# UBL_Distribution_V1p0.net
KiCad netlist of a schematic drawn in EAGLE
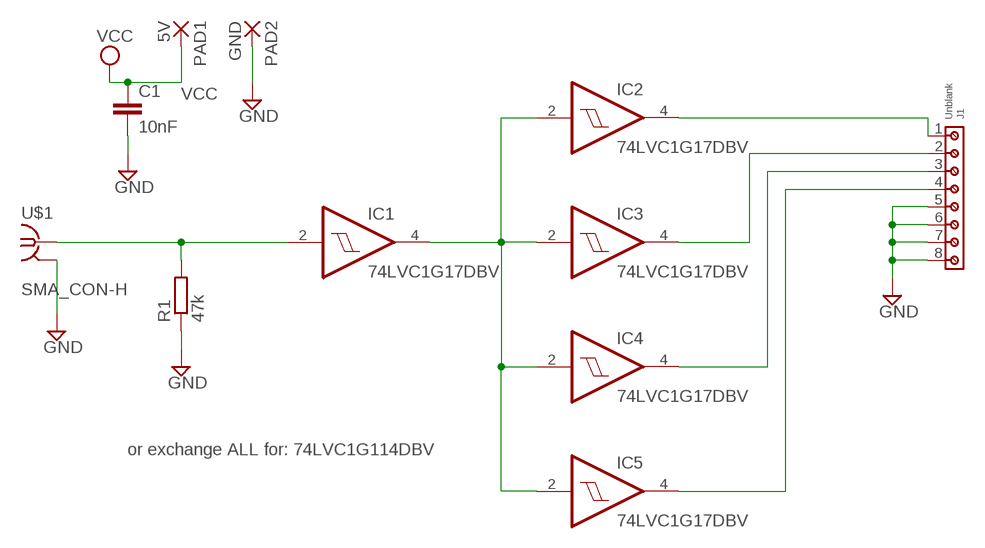
[diagram p0: schematic, sheet 1]

(export (version "E")
  (design (tool "Eeschema 10.0.6"))
  (components
    (comp (ref "C1")
      (value "10nF")
      (footprint "eagle-import:C0805")
      (libsource (lib "eagle-import") (part "C-EUC0805"))
    )
    (comp (ref "IC1")
      (value "74LVC1G17DBV")
      (footprint "eagle-import:SOT23-5")
      (libsource (lib "eagle-import") (part "741G17DBVLVC"))
    )
    (comp (ref "IC2")
      (value "74LVC1G17DBV")
      (footprint "eagle-import:SOT23-5")
      (libsource (lib "eagle-import") (part "741G17DBVLVC"))
    )
    (comp (ref "IC3")
      (value "74LVC1G17DBV")
      (footprint "eagle-import:SOT23-5")
      (libsource (lib "eagle-import") (part "741G17DBVLVC"))
    )
    (comp (ref "IC4")
      (value "74LVC1G17DBV")
      (footprint "eagle-import:SOT23-5")
      (libsource (lib "eagle-import") (part "741G17DBVLVC"))
    )
    (comp (ref "IC5")
      (value "74LVC1G17DBV")
      (footprint "eagle-import:SOT23-5")
      (libsource (lib "eagle-import") (part "741G17DBVLVC"))
    )
    (comp (ref "J1")
      (value "Unblank")
      (footprint "eagle-import:691210910008")
      (libsource (lib "eagle-import") (part "691210910008"))
    )
    (comp (ref "PAD1")
      (value "5V")
      (footprint "eagle-import:SMD2,54-5,08")
      (libsource (lib "eagle-import") (part "SMD5"))
    )
    (comp (ref "PAD2")
      (value "GND")
      (footprint "eagle-import:SMD2,54-5,08")
      (libsource (lib "eagle-import") (part "SMD5"))
    )
    (comp (ref "R1")
      (value "47k")
      (footprint "eagle-import:R0805")
      (libsource (lib "eagle-import") (part "R-EU_R0805"))
    )
    (comp (ref "U$1")
      (value "SMA_CON-H")
      (footprint "eagle-import:BU-SMA-H")
      (libsource (lib "eagle-import") (part "SMA_CON-H"))
    )
  )
  (nets
    (net (code "1") (name "GND") (class "Default")
      (node (ref "C1") (pin "2") (pinfunction "2_2") (pintype "passive"))
      (node (ref "J1") (pin "5") (pinfunction "5_5") (pintype "passive"))
      (node (ref "J1") (pin "6") (pinfunction "6_6") (pintype "passive"))
      (node (ref "J1") (pin "7") (pinfunction "7_7") (pintype "passive"))
      (node (ref "J1") (pin "8") (pinfunction "8_8") (pintype "passive"))
      (node (ref "PAD2") (pin "1") (pinfunction "P_1") (pintype "passive"))
      (node (ref "R1") (pin "1") (pinfunction "1_1") (pintype "passive"))
      (node (ref "U$1") (pin "2") (pinfunction "GND_2") (pintype "passive"))
      (node (ref "U$1") (pin "3") (pinfunction "GND_3") (pintype "passive"))
      (node (ref "U$1") (pin "4") (pinfunction "GND_4") (pintype "passive"))
      (node (ref "U$1") (pin "5") (pinfunction "GND_5") (pintype "passive"))
    )
    (net (code "2") (name "Net-(IC1A-I)") (class "Default")
      (node (ref "IC1") (pin "2") (pinfunction "I_2") (pintype "input"))
      (node (ref "R1") (pin "2") (pinfunction "2_2") (pintype "passive"))
      (node (ref "U$1") (pin "1") (pinfunction "1_1") (pintype "passive"))
    )
    (net (code "3") (name "Net-(IC1A-O)") (class "Default")
      (node (ref "IC1") (pin "4") (pinfunction "O_4") (pintype "output"))
      (node (ref "IC2") (pin "2") (pinfunction "I_2") (pintype "input"))
      (node (ref "IC3") (pin "2") (pinfunction "I_2") (pintype "input"))
      (node (ref "IC4") (pin "2") (pinfunction "I_2") (pintype "input"))
      (node (ref "IC5") (pin "2") (pinfunction "I_2") (pintype "input"))
    )
    (net (code "4") (name "Net-(IC2A-O)") (class "Default")
      (node (ref "IC2") (pin "4") (pinfunction "O_4") (pintype "output"))
      (node (ref "J1") (pin "1") (pinfunction "1_1") (pintype "passive"))
    )
    (net (code "5") (name "Net-(IC3A-O)") (class "Default")
      (node (ref "IC3") (pin "4") (pinfunction "O_4") (pintype "output"))
      (node (ref "J1") (pin "2") (pinfunction "2_2") (pintype "passive"))
    )
    (net (code "6") (name "Net-(IC4A-O)") (class "Default")
      (node (ref "IC4") (pin "4") (pinfunction "O_4") (pintype "output"))
      (node (ref "J1") (pin "3") (pinfunction "3_3") (pintype "passive"))
    )
    (net (code "7") (name "Net-(IC5A-O)") (class "Default")
      (node (ref "IC5") (pin "4") (pinfunction "O_4") (pintype "output"))
      (node (ref "J1") (pin "4") (pinfunction "4_4") (pintype "passive"))
    )
    (net (code "8") (name "VCC") (class "Default")
      (node (ref "C1") (pin "1") (pinfunction "1_1") (pintype "passive"))
      (node (ref "PAD1") (pin "1") (pinfunction "P_1") (pintype "passive"))
    )
  )
)
